# ds8.net
KiCad netlist of a schematic drawn in EAGLE
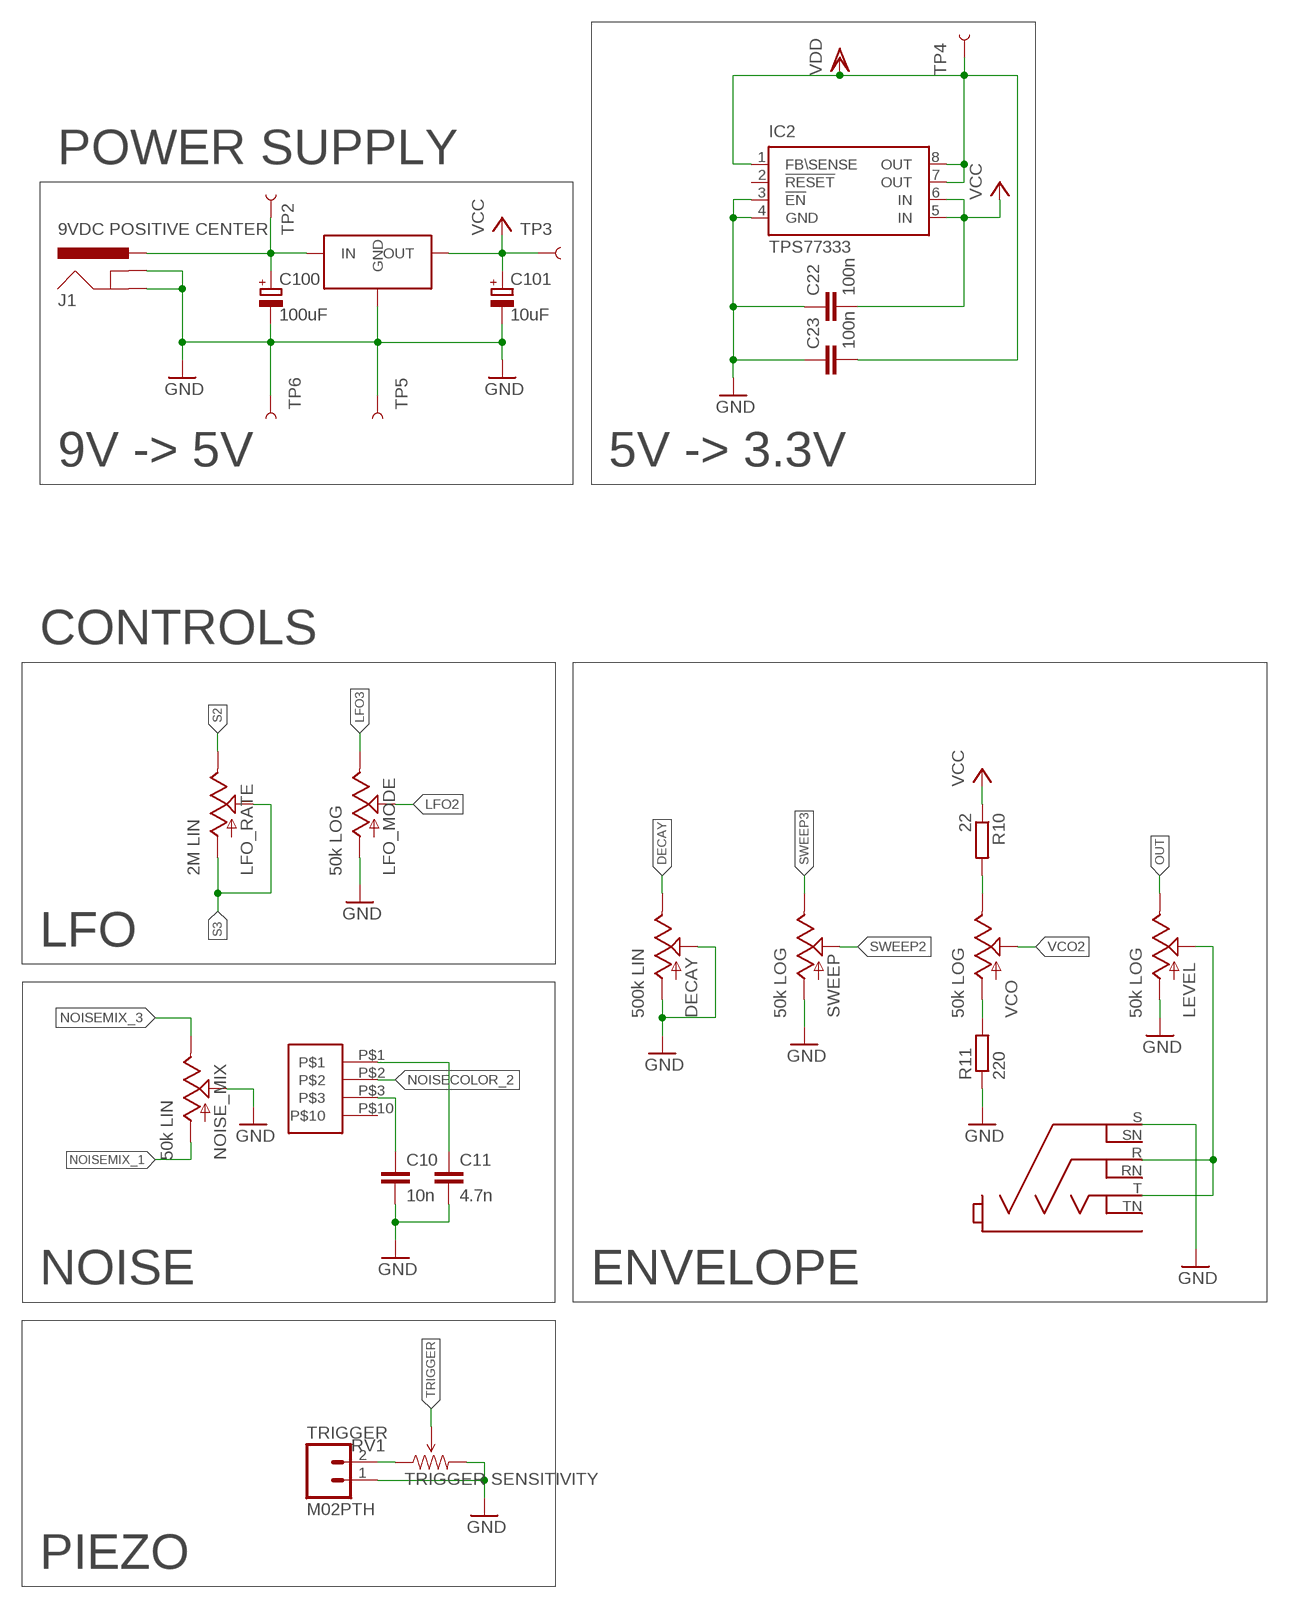
[diagram p0: schematic, sheet 1, part 1 of 2]
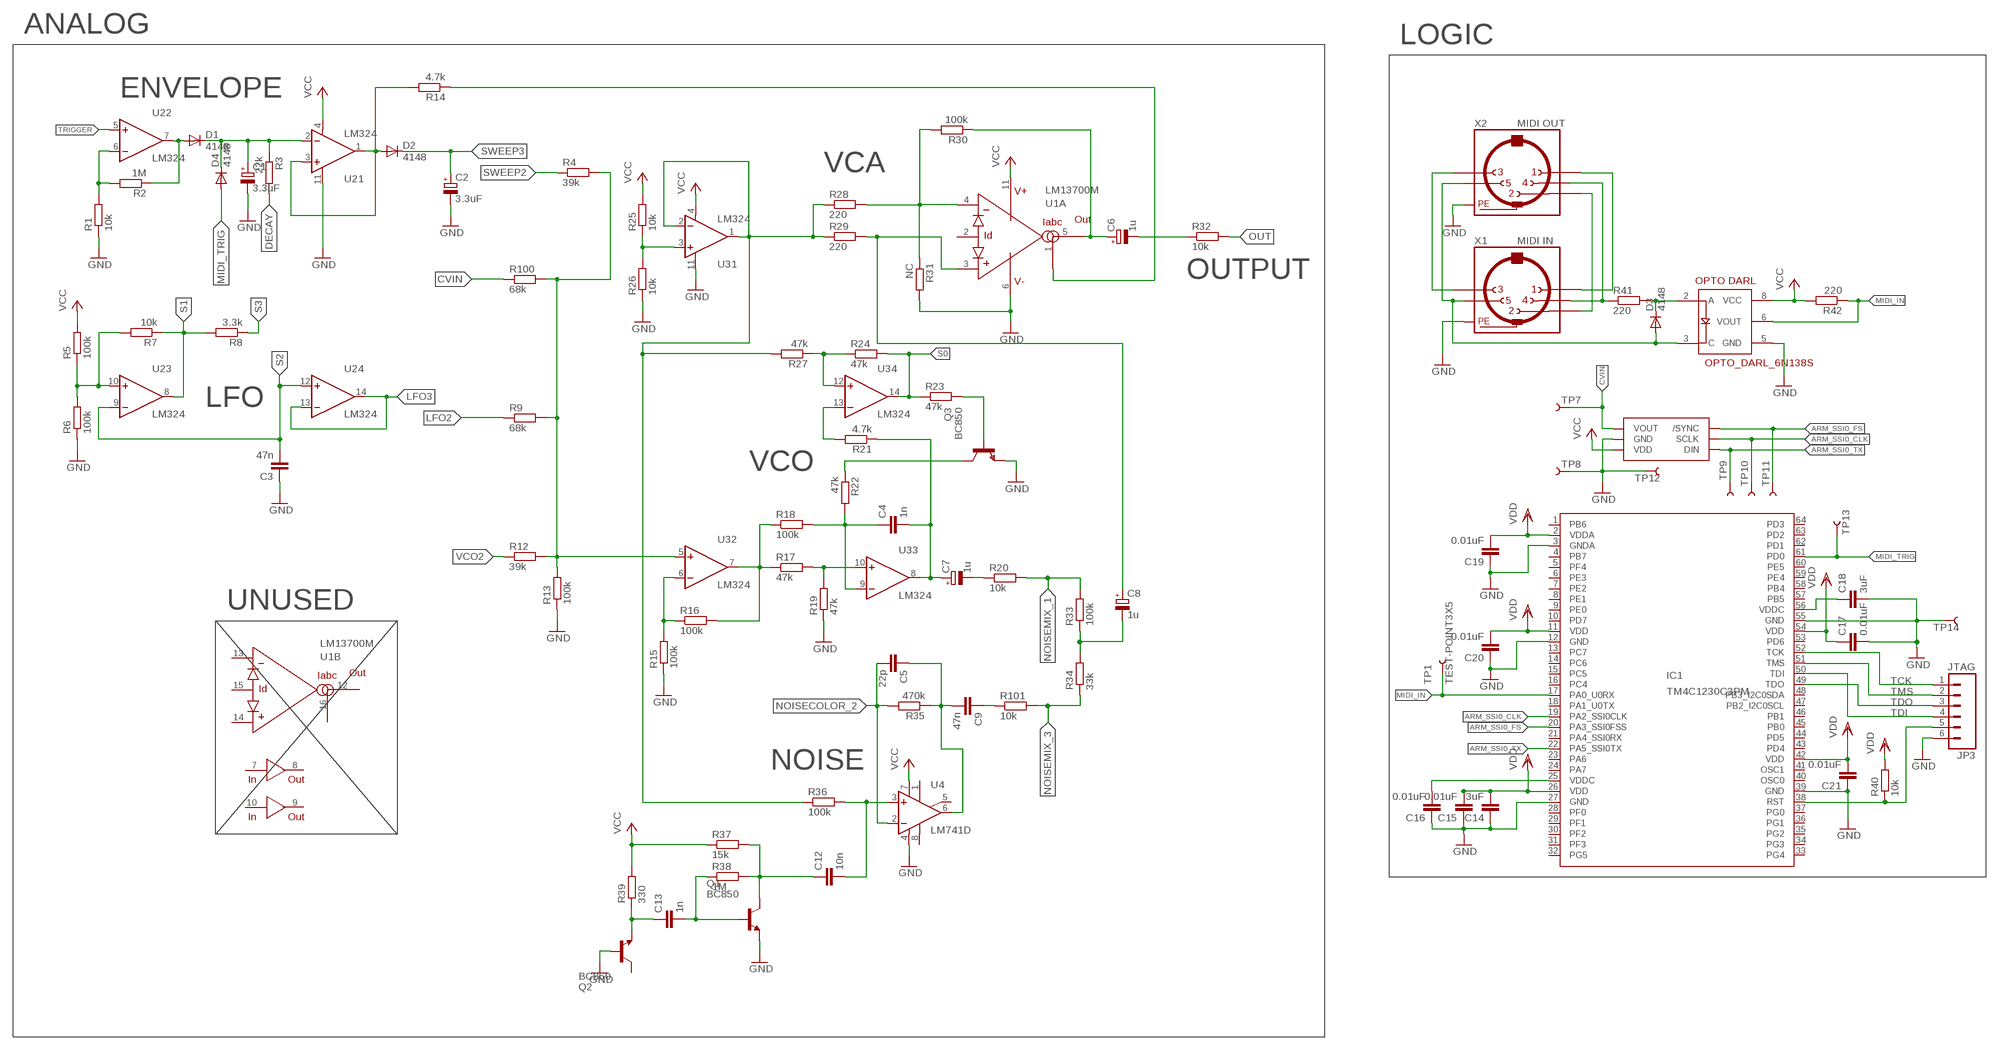
[diagram p1: schematic, sheet 1, part 2 of 2]

(export (version "E")
  (design (tool "Eeschema 10.0.6"))
  (components
    (comp (ref "C1")
      (value "3.3uF")
      (footprint "eagle-import:R_2012-12R")
      (libsource (lib "eagle-import") (part "CPOL-EUR/2012-12R"))
    )
    (comp (ref "C2")
      (value "3.3uF")
      (footprint "eagle-import:R_2012-12R")
      (libsource (lib "eagle-import") (part "CPOL-EUR/2012-12R"))
    )
    (comp (ref "C3")
      (value "47n")
      (footprint "eagle-import:C1206")
      (libsource (lib "eagle-import") (part "C-EUC1206"))
    )
    (comp (ref "C4")
      (value "1n")
      (footprint "eagle-import:C1206")
      (libsource (lib "eagle-import") (part "C-EUC1206"))
    )
    (comp (ref "C5")
      (value "22p")
      (footprint "eagle-import:C1206")
      (libsource (lib "eagle-import") (part "C-EUC1206"))
    )
    (comp (ref "C6")
      (value "1u")
      (footprint "eagle-import:R_2012-12R")
      (libsource (lib "eagle-import") (part "CPOL-EUR/2012-12R"))
    )
    (comp (ref "C7")
      (value "1u")
      (footprint "eagle-import:R_2012-12R")
      (libsource (lib "eagle-import") (part "CPOL-EUR/2012-12R"))
    )
    (comp (ref "C8")
      (value "1u")
      (footprint "eagle-import:R_2012-12R")
      (libsource (lib "eagle-import") (part "CPOL-EUR/2012-12R"))
    )
    (comp (ref "C9")
      (value "47n")
      (footprint "eagle-import:C1206")
      (libsource (lib "eagle-import") (part "C-EUC1206"))
    )
    (comp (ref "C10")
      (value "10n")
      (footprint "eagle-import:C1206")
      (libsource (lib "eagle-import") (part "C-EUC1206"))
    )
    (comp (ref "C11")
      (value "4.7n")
      (footprint "eagle-import:C1206")
      (libsource (lib "eagle-import") (part "C-EUC1206"))
    )
    (comp (ref "C12")
      (value "10n")
      (footprint "eagle-import:C1206")
      (libsource (lib "eagle-import") (part "C-EUC1206"))
    )
    (comp (ref "C13")
      (value "1n")
      (footprint "eagle-import:C1206")
      (libsource (lib "eagle-import") (part "C-EUC1206"))
    )
    (comp (ref "C14")
      (value "3uF")
      (footprint "eagle-import:C1206")
      (libsource (lib "eagle-import") (part "C-EUC1206"))
    )
    (comp (ref "C15")
      (value "0.01uF")
      (footprint "eagle-import:C1206")
      (libsource (lib "eagle-import") (part "C-EUC1206"))
    )
    (comp (ref "C16")
      (value "0.01uF")
      (footprint "eagle-import:C1206")
      (libsource (lib "eagle-import") (part "C-EUC1206"))
    )
    (comp (ref "C17")
      (value "0.01uF")
      (footprint "eagle-import:C1206")
      (libsource (lib "eagle-import") (part "C-EUC1206"))
    )
    (comp (ref "C18")
      (value "3uF")
      (footprint "eagle-import:C1206")
      (libsource (lib "eagle-import") (part "C-EUC1206"))
    )
    (comp (ref "C19")
      (value "0.01uF")
      (footprint "eagle-import:C1206")
      (libsource (lib "eagle-import") (part "C-EUC1206"))
    )
    (comp (ref "C20")
      (value "0.01uF")
      (footprint "eagle-import:C1206")
      (libsource (lib "eagle-import") (part "C-EUC1206"))
    )
    (comp (ref "C21")
      (value "0.01uF")
      (footprint "eagle-import:C1206")
      (libsource (lib "eagle-import") (part "C-EUC1206"))
    )
    (comp (ref "C22")
      (value "100n")
      (footprint "eagle-import:C1206")
      (libsource (lib "eagle-import") (part "C-EUC1206"))
    )
    (comp (ref "C23")
      (value "100n")
      (footprint "eagle-import:C1206")
      (libsource (lib "eagle-import") (part "C-EUC1206"))
    )
    (comp (ref "C100")
      (value "100uF")
      (footprint "eagle-import:PANASONIC_D")
      (libsource (lib "eagle-import") (part "CPOL-EUD"))
    )
    (comp (ref "C101")
      (value "10uF")
      (footprint "eagle-import:R_2012-12R")
      (libsource (lib "eagle-import") (part "CPOL-EUR/2012-12R"))
    )
    (comp (ref "D1")
      (value "4148")
      (footprint "eagle-import:MINIMELF")
      (libsource (lib "eagle-import") (part "DIODE-MINIMELF"))
    )
    (comp (ref "D2")
      (value "4148")
      (footprint "eagle-import:MINIMELF")
      (libsource (lib "eagle-import") (part "DIODE-MINIMELF"))
    )
    (comp (ref "D3")
      (value "4148")
      (footprint "eagle-import:MINIMELF")
      (libsource (lib "eagle-import") (part "DIODE-MINIMELF"))
    )
    (comp (ref "D4")
      (value "4148")
      (footprint "eagle-import:MINIMELF")
      (libsource (lib "eagle-import") (part "DIODE-MINIMELF"))
    )
    (comp (ref "DECAY")
      (value "500k LIN")
      (footprint "eagle-import:ALPS_POT_KIT")
      (libsource (lib "eagle-import") (part "POTALPS-KIT"))
    )
    (comp (ref "IC1")
      (value "TM4C1230C3PM")
      (footprint "eagle-import:LQFP_64")
      (libsource (lib "eagle-import") (part "TM4C1230C3PM"))
    )
    (comp (ref "IC2")
      (value "TPS77333")
      (footprint "eagle-import:SOP-08")
      (fields (field (name "MF") "TEXAS INSTRUMENTS") (field (name "MPN") "TPS77333DGK"))
      (libsource (lib "eagle-import") (part "TPS77333"))
    )
    (comp (ref "IC3")
      (value "DAC7512")
      (footprint "eagle-import:SOT-23-6")
      (libsource (lib "eagle-import") (part "DAC7512"))
    )
    (comp (ref "J1")
      (value "9VDC POSITIVE CENTER")
      (footprint "eagle-import:POWER_JACK_PTH_LOCK")
      (libsource (lib "eagle-import") (part "POWER_JACKPTH_LOCK"))
    )
    (comp (ref "JP3")
      (value "JTAG")
      (footprint "eagle-import:1X06")
      (libsource (lib "eagle-import") (part "M06SIP"))
    )
    (comp (ref "LEVEL")
      (value "50k LOG")
      (footprint "eagle-import:ALPS_POT_KIT")
      (libsource (lib "eagle-import") (part "POTALPS-KIT"))
    )
    (comp (ref "LFO_MODE")
      (value "50k LOG")
      (footprint "eagle-import:ALPS_POT_KIT")
      (libsource (lib "eagle-import") (part "POTALPS-KIT"))
    )
    (comp (ref "LFO_RATE")
      (value "2M LIN")
      (footprint "eagle-import:ALPS_POT_KIT")
      (libsource (lib "eagle-import") (part "POTALPS-KIT"))
    )
    (comp (ref "NOISE_MIX")
      (value "50k LIN")
      (footprint "eagle-import:ALPS_POT_KIT")
      (libsource (lib "eagle-import") (part "POTALPS-KIT"))
    )
    (comp (ref "Q1")
      (value "BC850")
      (footprint "eagle-import:SOT23")
      (libsource (lib "eagle-import") (part "BC850"))
    )
    (comp (ref "Q2")
      (value "BC850")
      (footprint "eagle-import:SOT23")
      (libsource (lib "eagle-import") (part "BC850"))
    )
    (comp (ref "Q3")
      (value "BC850")
      (footprint "eagle-import:SOT23")
      (libsource (lib "eagle-import") (part "BC850"))
    )
    (comp (ref "R1")
      (value "10k")
      (footprint "eagle-import:R0805")
      (libsource (lib "eagle-import") (part "R-EU_R0805"))
    )
    (comp (ref "R2")
      (value "1M")
      (footprint "eagle-import:R0805")
      (libsource (lib "eagle-import") (part "R-EU_R0805"))
    )
    (comp (ref "R3")
      (value "22k")
      (footprint "eagle-import:R0805")
      (libsource (lib "eagle-import") (part "R-EU_R0805"))
    )
    (comp (ref "R4")
      (value "39k")
      (footprint "eagle-import:R0805")
      (libsource (lib "eagle-import") (part "R-EU_R0805"))
    )
    (comp (ref "R5")
      (value "100k")
      (footprint "eagle-import:R0805")
      (libsource (lib "eagle-import") (part "R-EU_R0805"))
    )
    (comp (ref "R6")
      (value "100k")
      (footprint "eagle-import:R0805")
      (libsource (lib "eagle-import") (part "R-EU_R0805"))
    )
    (comp (ref "R7")
      (value "10k")
      (footprint "eagle-import:R0805")
      (libsource (lib "eagle-import") (part "R-EU_R0805"))
    )
    (comp (ref "R8")
      (value "3.3k")
      (footprint "eagle-import:R0805")
      (libsource (lib "eagle-import") (part "R-EU_R0805"))
    )
    (comp (ref "R9")
      (value "68k")
      (footprint "eagle-import:R0805")
      (libsource (lib "eagle-import") (part "R-EU_R0805"))
    )
    (comp (ref "R10")
      (value "22")
      (footprint "eagle-import:R0805")
      (libsource (lib "eagle-import") (part "R-EU_R0805"))
    )
    (comp (ref "R11")
      (value "220")
      (footprint "eagle-import:R0805")
      (libsource (lib "eagle-import") (part "R-EU_R0805"))
    )
    (comp (ref "R12")
      (value "39k")
      (footprint "eagle-import:R0805")
      (libsource (lib "eagle-import") (part "R-EU_R0805"))
    )
    (comp (ref "R13")
      (value "100k")
      (footprint "eagle-import:R0805")
      (libsource (lib "eagle-import") (part "R-EU_R0805"))
    )
    (comp (ref "R14")
      (value "4.7k")
      (footprint "eagle-import:R0805")
      (libsource (lib "eagle-import") (part "R-EU_R0805"))
    )
    (comp (ref "R15")
      (value "100k")
      (footprint "eagle-import:R0805")
      (libsource (lib "eagle-import") (part "R-EU_R0805"))
    )
    (comp (ref "R16")
      (value "100k")
      (footprint "eagle-import:M0805")
      (libsource (lib "eagle-import") (part "R-EU_M0805"))
    )
    (comp (ref "R17")
      (value "47k")
      (footprint "eagle-import:M0805")
      (libsource (lib "eagle-import") (part "R-EU_M0805"))
    )
    (comp (ref "R18")
      (value "100k")
      (footprint "eagle-import:M0805")
      (libsource (lib "eagle-import") (part "R-EU_M0805"))
    )
    (comp (ref "R19")
      (value "47k")
      (footprint "eagle-import:M0805")
      (libsource (lib "eagle-import") (part "R-EU_M0805"))
    )
    (comp (ref "R20")
      (value "10k")
      (footprint "eagle-import:M0805")
      (libsource (lib "eagle-import") (part "R-EU_M0805"))
    )
    (comp (ref "R21")
      (value "4.7k")
      (footprint "eagle-import:M0805")
      (libsource (lib "eagle-import") (part "R-EU_M0805"))
    )
    (comp (ref "R22")
      (value "47k")
      (footprint "eagle-import:M0805")
      (libsource (lib "eagle-import") (part "R-EU_M0805"))
    )
    (comp (ref "R23")
      (value "47k")
      (footprint "eagle-import:M0805")
      (libsource (lib "eagle-import") (part "R-EU_M0805"))
    )
    (comp (ref "R24")
      (value "47k")
      (footprint "eagle-import:M0805")
      (libsource (lib "eagle-import") (part "R-EU_M0805"))
    )
    (comp (ref "R25")
      (value "10k")
      (footprint "eagle-import:M0805")
      (libsource (lib "eagle-import") (part "R-EU_M0805"))
    )
    (comp (ref "R26")
      (value "10k")
      (footprint "eagle-import:M0805")
      (libsource (lib "eagle-import") (part "R-EU_M0805"))
    )
    (comp (ref "R27")
      (value "47k")
      (footprint "eagle-import:M0805")
      (libsource (lib "eagle-import") (part "R-EU_M0805"))
    )
    (comp (ref "R28")
      (value "220")
      (footprint "eagle-import:M0805")
      (libsource (lib "eagle-import") (part "R-EU_M0805"))
    )
    (comp (ref "R29")
      (value "220")
      (footprint "eagle-import:M0805")
      (libsource (lib "eagle-import") (part "R-EU_M0805"))
    )
    (comp (ref "R30")
      (value "100k")
      (footprint "eagle-import:M0805")
      (libsource (lib "eagle-import") (part "R-EU_M0805"))
    )
    (comp (ref "R31")
      (value "NC")
      (footprint "eagle-import:M0805")
      (libsource (lib "eagle-import") (part "R-EU_M0805"))
    )
    (comp (ref "R32")
      (value "10k")
      (footprint "eagle-import:M0805")
      (libsource (lib "eagle-import") (part "R-EU_M0805"))
    )
    (comp (ref "R33")
      (value "100k")
      (footprint "eagle-import:M0805")
      (libsource (lib "eagle-import") (part "R-EU_M0805"))
    )
    (comp (ref "R34")
      (value "33k")
      (footprint "eagle-import:M0805")
      (libsource (lib "eagle-import") (part "R-EU_M0805"))
    )
    (comp (ref "R35")
      (value "470k")
      (footprint "eagle-import:M0805")
      (libsource (lib "eagle-import") (part "R-EU_M0805"))
    )
    (comp (ref "R36")
      (value "100k")
      (footprint "eagle-import:M0805")
      (libsource (lib "eagle-import") (part "R-EU_M0805"))
    )
    (comp (ref "R37")
      (value "15k")
      (footprint "eagle-import:M0805")
      (libsource (lib "eagle-import") (part "R-EU_M0805"))
    )
    (comp (ref "R38")
      (value "1M")
      (footprint "eagle-import:M0805")
      (libsource (lib "eagle-import") (part "R-EU_M0805"))
    )
    (comp (ref "R39")
      (value "330")
      (footprint "eagle-import:M0805")
      (libsource (lib "eagle-import") (part "R-EU_M0805"))
    )
    (comp (ref "R40")
      (value "10k")
      (footprint "eagle-import:M0805")
      (libsource (lib "eagle-import") (part "R-EU_M0805"))
    )
    (comp (ref "R41")
      (value "220")
      (footprint "eagle-import:R0805")
      (libsource (lib "eagle-import") (part "R-EU_R0805"))
    )
    (comp (ref "R42")
      (value "220")
      (footprint "eagle-import:R0805")
      (libsource (lib "eagle-import") (part "R-EU_R0805"))
    )
    (comp (ref "R100")
      (value "68k")
      (footprint "eagle-import:R0805")
      (libsource (lib "eagle-import") (part "R-EU_R0805"))
    )
    (comp (ref "R101")
      (value "10k")
      (footprint "eagle-import:M0805")
      (libsource (lib "eagle-import") (part "R-EU_M0805"))
    )
    (comp (ref "RV1")
      (value "TRIGGER SENSITIVITY")
      (footprint "eagle-import:TRIMPOT-5MM-V2")
      (libsource (lib "eagle-import") (part "TRIMPOT"))
    )
    (comp (ref "SWEEP")
      (value "50k LOG")
      (footprint "eagle-import:ALPS_POT_KIT")
      (libsource (lib "eagle-import") (part "POTALPS-KIT"))
    )
    (comp (ref "TP1")
      (value "TEST-POINT3X5")
      (footprint "eagle-import:PAD.03X.05")
      (libsource (lib "eagle-import") (part "TEST-POINT3X5"))
    )
    (comp (ref "TP2")
      (value "TEST-POINT3X5")
      (footprint "eagle-import:PAD.03X.05")
      (libsource (lib "eagle-import") (part "TEST-POINT3X5"))
    )
    (comp (ref "TP3")
      (value "TEST-POINT3X5")
      (footprint "eagle-import:PAD.03X.05")
      (libsource (lib "eagle-import") (part "TEST-POINT3X5"))
    )
    (comp (ref "TP4")
      (value "TEST-POINT3X5")
      (footprint "eagle-import:PAD.03X.05")
      (libsource (lib "eagle-import") (part "TEST-POINT3X5"))
    )
    (comp (ref "TP5")
      (value "TEST-POINT3X5")
      (footprint "eagle-import:PAD.03X.05")
      (libsource (lib "eagle-import") (part "TEST-POINT3X5"))
    )
    (comp (ref "TP6")
      (value "TEST-POINT3X5")
      (footprint "eagle-import:PAD.03X.05")
      (libsource (lib "eagle-import") (part "TEST-POINT3X5"))
    )
    (comp (ref "TP7")
      (value "TEST-POINT3X5")
      (footprint "eagle-import:PAD.03X.05")
      (libsource (lib "eagle-import") (part "TEST-POINT3X5"))
    )
    (comp (ref "TP8")
      (value "TEST-POINT3X5")
      (footprint "eagle-import:PAD.03X.05")
      (libsource (lib "eagle-import") (part "TEST-POINT3X5"))
    )
    (comp (ref "TP9")
      (value "TEST-POINT3X5")
      (footprint "eagle-import:PAD.03X.05")
      (libsource (lib "eagle-import") (part "TEST-POINT3X5"))
    )
    (comp (ref "TP10")
      (value "TEST-POINT3X5")
      (footprint "eagle-import:PAD.03X.05")
      (libsource (lib "eagle-import") (part "TEST-POINT3X5"))
    )
    (comp (ref "TP11")
      (value "TEST-POINT3X5")
      (footprint "eagle-import:PAD.03X.05")
      (libsource (lib "eagle-import") (part "TEST-POINT3X5"))
    )
    (comp (ref "TP12")
      (value "TEST-POINT3X5")
      (footprint "eagle-import:PAD.03X.05")
      (libsource (lib "eagle-import") (part "TEST-POINT3X5"))
    )
    (comp (ref "TP13")
      (value "TEST-POINT3X5")
      (footprint "eagle-import:PAD.03X.05")
      (libsource (lib "eagle-import") (part "TEST-POINT3X5"))
    )
    (comp (ref "TP14")
      (value "TEST-POINT3X5")
      (footprint "eagle-import:PAD.03X.05")
      (libsource (lib "eagle-import") (part "TEST-POINT3X5"))
    )
    (comp (ref "TRIGGER")
      (value "M02PTH")
      (footprint "eagle-import:1X02")
      (libsource (lib "eagle-import") (part "M02PTH"))
    )
    (comp (ref "U$1")
      (value "6.35MMJACK")
      (footprint "eagle-import:NMJ6HCD3")
      (libsource (lib "eagle-import") (part "6.35MMJACK"))
    )
    (comp (ref "U$3")
      (value "ALPS_SRBV")
      (footprint "eagle-import:ALPS_SRBV")
      (libsource (lib "eagle-import") (part "ALPS_SRBV"))
    )
    (comp (ref "U$4")
      (value "OPTO_DARL_6N138S")
      (footprint "eagle-import:8-SMD")
      (libsource (lib "eagle-import") (part "OPTO_DARL_6N138S"))
    )
    (comp (ref "U1")
      (value "LM13700M")
      (footprint "eagle-import:DS8_SO16")
      (libsource (lib "eagle-import") (part "DS8_LM13700M"))
    )
    (comp (ref "U2")
      (value "LM324")
      (footprint "eagle-import:SOIC-14")
      (libsource (lib "eagle-import") (part "LM324"))
    )
    (comp (ref "U3")
      (value "LM324")
      (footprint "eagle-import:SOIC-14")
      (libsource (lib "eagle-import") (part "LM324"))
    )
    (comp (ref "U4")
      (value "LM741D")
      (footprint "eagle-import:SO08")
      (libsource (lib "eagle-import") (part "741DLM"))
    )
    (comp (ref "U100")
      (value "VREG-7805-DPAK2")
      (footprint "eagle-import:VREG-7805-DPAK2")
      (libsource (lib "eagle-import") (part "VREG-7805-DPAK2"))
    )
    (comp (ref "VCO")
      (value "50k LOG")
      (footprint "eagle-import:ALPS_POT_KIT")
      (libsource (lib "eagle-import") (part "POTALPS-KIT"))
    )
    (comp (ref "X1")
      (value "MIDI IN")
      (footprint "eagle-import:MAB5SH")
      (libsource (lib "eagle-import") (part "MAB5SH"))
    )
    (comp (ref "X2")
      (value "MIDI OUT")
      (footprint "eagle-import:MAB5SH")
      (fields (field (name "OC_FARNELL") "809883") (field (name "OC_NEWARK") "unknown"))
      (libsource (lib "eagle-import") (part "MAB5SH"))
    )
  )
  (nets
    (net (code "1") (name "/TCK") (class "Default")
      (node (ref "IC1") (pin "52") (pinfunction "TCK_52") (pintype "input"))
      (node (ref "JP3") (pin "1") (pinfunction "1_1") (pintype "passive"))
    )
    (net (code "2") (name "/TDI") (class "Default")
      (node (ref "IC1") (pin "50") (pinfunction "TDI_50") (pintype "input"))
      (node (ref "JP3") (pin "4") (pinfunction "4_4") (pintype "passive"))
    )
    (net (code "3") (name "/TDO") (class "Default")
      (node (ref "IC1") (pin "49") (pinfunction "TDO_49") (pintype "output"))
      (node (ref "JP3") (pin "3") (pinfunction "3_3") (pintype "passive"))
    )
    (net (code "4") (name "/TMS") (class "Default")
      (node (ref "IC1") (pin "51") (pinfunction "TMS_51") (pintype "input"))
      (node (ref "JP3") (pin "2") (pinfunction "2_2") (pintype "passive"))
    )
    (net (code "5") (name "ARM_SSI0_CLK") (class "Default")
      (node (ref "IC1") (pin "19") (pinfunction "PA2_SSI0CLK_19") (pintype "bidirectional"))
      (node (ref "IC3") (pin "5") (pinfunction "SCLK_5") (pintype "bidirectional"))
      (node (ref "TP10") (pin "P$1") (pinfunction "1_P$1") (pintype "bidirectional"))
    )
    (net (code "6") (name "ARM_SSI0_FS") (class "Default")
      (node (ref "IC1") (pin "20") (pinfunction "PA3_SSI0FSS_20") (pintype "bidirectional"))
      (node (ref "IC3") (pin "6") (pinfunction "/SYNC_6") (pintype "bidirectional"))
      (node (ref "TP11") (pin "P$1") (pinfunction "1_P$1") (pintype "bidirectional"))
    )
    (net (code "7") (name "ARM_SSI0_TX") (class "Default")
      (node (ref "IC1") (pin "22") (pinfunction "PA5_SSI0TX_22") (pintype "bidirectional"))
      (node (ref "IC3") (pin "4") (pinfunction "DIN_4") (pintype "bidirectional"))
      (node (ref "TP9") (pin "P$1") (pinfunction "1_P$1") (pintype "bidirectional"))
    )
    (net (code "8") (name "CVIN") (class "Default")
      (node (ref "IC3") (pin "1") (pinfunction "VOUT_1") (pintype "output"))
      (node (ref "R100") (pin "1") (pinfunction "1_1") (pintype "passive"))
      (node (ref "TP7") (pin "P$1") (pinfunction "1_P$1") (pintype "bidirectional"))
    )
    (net (code "9") (name "DECAY") (class "Default")
      (node (ref "DECAY") (pin "P$1") (pinfunction "E_P$1") (pintype "passive"))
      (node (ref "R3") (pin "2") (pinfunction "2_2") (pintype "passive"))
    )
    (net (code "10") (name "GND") (class "Default")
      (node (ref "C1") (pin "-") (pinfunction "-_-") (pintype "passive"))
      (node (ref "C10") (pin "2") (pinfunction "2_2") (pintype "passive"))
      (node (ref "C100") (pin "-") (pinfunction "-_-") (pintype "passive"))
      (node (ref "C101") (pin "-") (pinfunction "-_-") (pintype "passive"))
      (node (ref "C11") (pin "2") (pinfunction "2_2") (pintype "passive"))
      (node (ref "C14") (pin "1") (pinfunction "1_1") (pintype "passive"))
      (node (ref "C15") (pin "1") (pinfunction "1_1") (pintype "passive"))
      (node (ref "C16") (pin "1") (pinfunction "1_1") (pintype "passive"))
      (node (ref "C17") (pin "2") (pinfunction "2_2") (pintype "passive"))
      (node (ref "C18") (pin "2") (pinfunction "2_2") (pintype "passive"))
      (node (ref "C19") (pin "1") (pinfunction "1_1") (pintype "passive"))
      (node (ref "C2") (pin "-") (pinfunction "-_-") (pintype "passive"))
      (node (ref "C20") (pin "1") (pinfunction "1_1") (pintype "passive"))
      (node (ref "C21") (pin "1") (pinfunction "1_1") (pintype "passive"))
      (node (ref "C22") (pin "1") (pinfunction "1_1") (pintype "passive"))
      (node (ref "C23") (pin "1") (pinfunction "1_1") (pintype "passive"))
      (node (ref "C3") (pin "1") (pinfunction "1_1") (pintype "passive"))
      (node (ref "DECAY") (pin "P$2") (pinfunction "S_P$2") (pintype "passive"))
      (node (ref "DECAY") (pin "P$3") (pinfunction "A_P$3") (pintype "passive"))
      (node (ref "IC1") (pin "12") (pinfunction "GND_12") (pintype "power_in"))
      (node (ref "IC1") (pin "27") (pinfunction "GND_27") (pintype "power_in"))
      (node (ref "IC1") (pin "3") (pinfunction "GNDA_3") (pintype "power_in"))
      (node (ref "IC1") (pin "39") (pinfunction "GND_39") (pintype "power_in"))
      (node (ref "IC1") (pin "55") (pinfunction "GND_55") (pintype "power_in"))
      (node (ref "IC2") (pin "3") (pinfunction "~{EN}_3") (pintype "input"))
      (node (ref "IC2") (pin "4") (pinfunction "GND_4") (pintype "power_in"))
      (node (ref "IC3") (pin "2") (pinfunction "GND_2") (pintype "power_in"))
      (node (ref "J1") (pin "GND") (pinfunction "GND_GND") (pintype "bidirectional"))
      (node (ref "J1") (pin "GNDBREAK") (pinfunction "GNDBREAK_GNDBREAK") (pintype "bidirectional"))
      (node (ref "JP3") (pin "6") (pinfunction "6_6") (pintype "passive"))
      (node (ref "LEVEL") (pin "P$3") (pinfunction "A_P$3") (pintype "passive"))
      (node (ref "LFO_MODE") (pin "P$3") (pinfunction "A_P$3") (pintype "passive"))
      (node (ref "NOISE_MIX") (pin "P$2") (pinfunction "S_P$2") (pintype "passive"))
      (node (ref "Q1") (pin "2") (pinfunction "E_2") (pintype "passive"))
      (node (ref "Q2") (pin "1") (pinfunction "B_1") (pintype "passive"))
      (node (ref "Q3") (pin "2") (pinfunction "E_2") (pintype "passive"))
      (node (ref "R1") (pin "1") (pinfunction "1_1") (pintype "passive"))
      (node (ref "R11") (pin "1") (pinfunction "1_1") (pintype "passive"))
      (node (ref "R13") (pin "1") (pinfunction "1_1") (pintype "passive"))
      (node (ref "R15") (pin "1") (pinfunction "1_1") (pintype "passive"))
      (node (ref "R19") (pin "1") (pinfunction "1_1") (pintype "passive"))
      (node (ref "R26") (pin "1") (pinfunction "1_1") (pintype "passive"))
      (node (ref "R31") (pin "2") (pinfunction "2_2") (pintype "passive"))
      (node (ref "R6") (pin "1") (pinfunction "1_1") (pintype "passive"))
      (node (ref "RV1") (pin "C") (pinfunction "CW_C") (pintype "passive"))
      (node (ref "SWEEP") (pin "P$3") (pinfunction "A_P$3") (pintype "passive"))
      (node (ref "TP12") (pin "P$1") (pinfunction "1_P$1") (pintype "bidirectional"))
      (node (ref "TP14") (pin "P$1") (pinfunction "1_P$1") (pintype "bidirectional"))
      (node (ref "TP5") (pin "P$1") (pinfunction "1_P$1") (pintype "bidirectional"))
      (node (ref "TP6") (pin "P$1") (pinfunction "1_P$1") (pintype "bidirectional"))
      (node (ref "TP8") (pin "P$1") (pinfunction "1_P$1") (pintype "bidirectional"))
      (node (ref "TRIGGER") (pin "1") (pinfunction "1_1") (pintype "passive"))
      (node (ref "U$1") (pin "S") (pinfunction "S_S") (pintype "bidirectional"))
      (node (ref "U$4") (pin "5") (pinfunction "GND_5") (pintype "bidirectional"))
      (node (ref "U1") (pin "6") (pinfunction "V-_6") (pintype "bidirectional"))
      (node (ref "U100") (pin "GND") (pinfunction "GND_GND") (pintype "bidirectional"))
      (node (ref "U2") (pin "11") (pinfunction "V-_11") (pintype "power_in"))
      (node (ref "U3") (pin "11") (pinfunction "V-_11") (pintype "power_in"))
      (node (ref "U4") (pin "4") (pinfunction "V-_4") (pintype "power_in"))
      (node (ref "X1") (pin "PE") (pinfunction "PE_PE") (pintype "power_in"))
      (node (ref "X1") (pin "PE@") (pinfunction "PE_PE@") (pintype "power_in"))
      (node (ref "X2") (pin "PE") (pinfunction "PE_PE") (pintype "power_in"))
      (node (ref "X2") (pin "PE@") (pinfunction "PE_PE@") (pintype "power_in"))
    )
    (net (code "11") (name "LFO2") (class "Default")
      (node (ref "LFO_MODE") (pin "P$2") (pinfunction "S_P$2") (pintype "passive"))
      (node (ref "R9") (pin "1") (pinfunction "1_1") (pintype "passive"))
    )
    (net (code "12") (name "LFO3") (class "Default")
      (node (ref "LFO_MODE") (pin "P$1") (pinfunction "E_P$1") (pintype "passive"))
      (node (ref "U2") (pin "13") (pinfunction "-IN_13") (pintype "input"))
      (node (ref "U2") (pin "14") (pinfunction "OUT_14") (pintype "output"))
    )
    (net (code "13") (name "MIDI_IN") (class "Default")
      (node (ref "IC1") (pin "17") (pinfunction "PA0_U0RX_17") (pintype "bidirectional"))
      (node (ref "R42") (pin "1") (pinfunction "1_1") (pintype "passive"))
      (node (ref "TP1") (pin "P$1") (pinfunction "1_P$1") (pintype "bidirectional"))
      (node (ref "U$4") (pin "6") (pinfunction "VOUT_6") (pintype "bidirectional"))
    )
    (net (code "14") (name "MIDI_TRIG") (class "Default")
      (node (ref "D4") (pin "A") (pinfunction "A_A") (pintype "passive"))
      (node (ref "IC1") (pin "61") (pinfunction "PD0_61") (pintype "bidirectional"))
      (node (ref "TP13") (pin "P$1") (pinfunction "1_P$1") (pintype "bidirectional"))
    )
    (net (code "15") (name "NOISECOLOR_2") (class "Default")
      (node (ref "C5") (pin "2") (pinfunction "2_2") (pintype "passive"))
      (node (ref "R35") (pin "2") (pinfunction "2_2") (pintype "passive"))
      (node (ref "U$3") (pin "P$2") (pinfunction "P$2_P$2") (pintype "bidirectional"))
      (node (ref "U4") (pin "2") (pinfunction "-IN_2") (pintype "input"))
    )
    (net (code "16") (name "NOISEMIX_1") (class "Default")
      (node (ref "NOISE_MIX") (pin "P$3") (pinfunction "A_P$3") (pintype "passive"))
      (node (ref "R20") (pin "2") (pinfunction "2_2") (pintype "passive"))
      (node (ref "R33") (pin "2") (pinfunction "2_2") (pintype "passive"))
    )
    (net (code "17") (name "NOISEMIX_3") (class "Default")
      (node (ref "NOISE_MIX") (pin "P$1") (pinfunction "E_P$1") (pintype "passive"))
      (node (ref "R101") (pin "2") (pinfunction "2_2") (pintype "passive"))
      (node (ref "R34") (pin "1") (pinfunction "1_1") (pintype "passive"))
    )
    (net (code "18") (name "Net-(C6-Pad-)") (class "Default")
      (node (ref "C6") (pin "-") (pinfunction "-_-") (pintype "passive"))
      (node (ref "R32") (pin "1") (pinfunction "1_1") (pintype "passive"))
    )
    (net (code "19") (name "Net-(C7-Pad-)") (class "Default")
      (node (ref "C7") (pin "-") (pinfunction "-_-") (pintype "passive"))
      (node (ref "R20") (pin "1") (pinfunction "1_1") (pintype "passive"))
    )
    (net (code "20") (name "Net-(C8-Pad-)") (class "Default")
      (node (ref "C8") (pin "-") (pinfunction "-_-") (pintype "passive"))
      (node (ref "R33") (pin "1") (pinfunction "1_1") (pintype "passive"))
      (node (ref "R34") (pin "2") (pinfunction "2_2") (pintype "passive"))
    )
    (net (code "21") (name "Net-(C9-Pad1)") (class "Default")
      (node (ref "C9") (pin "1") (pinfunction "1_1") (pintype "passive"))
      (node (ref "R101") (pin "1") (pinfunction "1_1") (pintype "passive"))
    )
    (net (code "22") (name "Net-(C10-Pad1)") (class "Default")
      (node (ref "C10") (pin "1") (pinfunction "1_1") (pintype "passive"))
      (node (ref "U$3") (pin "P$3") (pinfunction "P$3_P$3") (pintype "bidirectional"))
    )
    (net (code "23") (name "Net-(C11-Pad1)") (class "Default")
      (node (ref "C11") (pin "1") (pinfunction "1_1") (pintype "passive"))
      (node (ref "U$3") (pin "P$1") (pinfunction "P$1_P$1") (pintype "bidirectional"))
    )
    (net (code "24") (name "Net-(C16-Pad2)") (class "Default")
      (node (ref "C16") (pin "2") (pinfunction "2_2") (pintype "passive"))
      (node (ref "IC1") (pin "25") (pinfunction "VDDC_25") (pintype "power_in"))
    )
    (net (code "25") (name "Net-(C18-Pad1)") (class "Default")
      (node (ref "C18") (pin "1") (pinfunction "1_1") (pintype "passive"))
      (node (ref "IC1") (pin "56") (pinfunction "VDDC_56") (pintype "power_in"))
    )
    (net (code "26") (name "Net-(IC1-RST)") (class "Default")
      (node (ref "IC1") (pin "38") (pinfunction "RST_38") (pintype "passive"))
      (node (ref "JP3") (pin "5") (pinfunction "5_5") (pintype "passive"))
      (node (ref "R40") (pin "1") (pinfunction "1_1") (pintype "passive"))
    )
    (net (code "27") (name "Net-(LEVEL-S)") (class "Default")
      (node (ref "LEVEL") (pin "P$2") (pinfunction "S_P$2") (pintype "passive"))
      (node (ref "U$1") (pin "R") (pinfunction "R_R") (pintype "bidirectional"))
      (node (ref "U$1") (pin "T") (pinfunction "T_T") (pintype "bidirectional"))
    )
    (net (code "28") (name "Net-(Q1-B)") (class "Default")
      (node (ref "C13") (pin "2") (pinfunction "2_2") (pintype "passive"))
      (node (ref "Q1") (pin "1") (pinfunction "B_1") (pintype "passive"))
      (node (ref "R38") (pin "1") (pinfunction "1_1") (pintype "passive"))
    )
    (net (code "29") (name "Net-(Q1-C)") (class "Default")
      (node (ref "C12") (pin "1") (pinfunction "1_1") (pintype "passive"))
      (node (ref "Q1") (pin "3") (pinfunction "C_3") (pintype "passive"))
      (node (ref "R37") (pin "2") (pinfunction "2_2") (pintype "passive"))
      (node (ref "R38") (pin "2") (pinfunction "2_2") (pintype "passive"))
    )
    (net (code "30") (name "Net-(Q2-E)") (class "Default")
      (node (ref "C13") (pin "1") (pinfunction "1_1") (pintype "passive"))
      (node (ref "Q2") (pin "2") (pinfunction "E_2") (pintype "passive"))
      (node (ref "R39") (pin "1") (pinfunction "1_1") (pintype "passive"))
    )
    (net (code "31") (name "Net-(Q3-B)") (class "Default")
      (node (ref "Q3") (pin "1") (pinfunction "B_1") (pintype "passive"))
      (node (ref "R23") (pin "2") (pinfunction "2_2") (pintype "passive"))
    )
    (net (code "32") (name "Net-(Q3-C)") (class "Default")
      (node (ref "Q3") (pin "3") (pinfunction "C_3") (pintype "passive"))
      (node (ref "R22") (pin "1") (pinfunction "1_1") (pintype "passive"))
    )
    (net (code "33") (name "Net-(R41-Pad1)") (class "Default")
      (node (ref "R41") (pin "1") (pinfunction "1_1") (pintype "passive"))
      (node (ref "X1") (pin "4") (pinfunction "4_4") (pintype "passive"))
      (node (ref "X2") (pin "4") (pinfunction "4_4") (pintype "passive"))
    )
    (net (code "34") (name "Net-(RV1-CCW)") (class "Default")
      (node (ref "RV1") (pin "A") (pinfunction "CCW_A") (pintype "passive"))
      (node (ref "TRIGGER") (pin "2") (pinfunction "2_2") (pintype "passive"))
    )
    (net (code "35") (name "Net-(TP2-1)") (class "Default")
      (node (ref "C100") (pin "+") (pinfunction "+_+") (pintype "passive"))
      (node (ref "J1") (pin "PWR") (pinfunction "PWR_PWR") (pintype "bidirectional"))
      (node (ref "TP2") (pin "P$1") (pinfunction "1_P$1") (pintype "bidirectional"))
      (node (ref "U100") (pin "VIN") (pinfunction "IN_VIN") (pintype "bidirectional"))
    )
    (net (code "36") (name "Net-(U$4-A)") (class "Default")
      (node (ref "D3") (pin "C") (pinfunction "C_C") (pintype "passive"))
      (node (ref "R41") (pin "2") (pinfunction "2_2") (pintype "passive"))
      (node (ref "U$4") (pin "2") (pinfunction "A_2") (pintype "bidirectional"))
    )
    (net (code "37") (name "Net-(U$4-C)") (class "Default")
      (node (ref "D3") (pin "A") (pinfunction "A_A") (pintype "passive"))
      (node (ref "U$4") (pin "3") (pinfunction "C_3") (pintype "bidirectional"))
      (node (ref "X1") (pin "5") (pinfunction "5_5") (pintype "passive"))
      (node (ref "X2") (pin "5") (pinfunction "5_5") (pintype "passive"))
    )
    (net (code "38") (name "Net-(U1A-+IN)") (class "Default")
      (node (ref "C8") (pin "+") (pinfunction "+_+") (pintype "passive"))
      (node (ref "R29") (pin "2") (pinfunction "2_2") (pintype "passive"))
      (node (ref "U1") (pin "3") (pinfunction "+IN_3") (pintype "bidirectional"))
    )
    (net (code "39") (name "Net-(U1A--IN)") (class "Default")
      (node (ref "R28") (pin "2") (pinfunction "2_2") (pintype "passive"))
      (node (ref "R30") (pin "2") (pinfunction "2_2") (pintype "passive"))
      (node (ref "R31") (pin "1") (pinfunction "1_1") (pintype "passive"))
      (node (ref "U1") (pin "4") (pinfunction "-IN_4") (pintype "bidirectional"))
    )
    (net (code "40") (name "Net-(U1A-IABC)") (class "Default")
      (node (ref "R14") (pin "1") (pinfunction "1_1") (pintype "passive"))
      (node (ref "U1") (pin "1") (pinfunction "IABC_1") (pintype "bidirectional"))
    )
    (net (code "41") (name "Net-(U1A-OUT)") (class "Default")
      (node (ref "C6") (pin "+") (pinfunction "+_+") (pintype "passive"))
      (node (ref "R30") (pin "1") (pinfunction "1_1") (pintype "passive"))
      (node (ref "U1") (pin "5") (pinfunction "OUT_5") (pintype "bidirectional"))
    )
    (net (code "42") (name "Net-(U2A-+IN)") (class "Default")
      (node (ref "D2") (pin "A") (pinfunction "A_A") (pintype "passive"))
      (node (ref "R14") (pin "2") (pinfunction "2_2") (pintype "passive"))
      (node (ref "U2") (pin "1") (pinfunction "OUT_1") (pintype "output"))
      (node (ref "U2") (pin "3") (pinfunction "+IN_3") (pintype "input"))
    )
    (net (code "43") (name "Net-(U2A--IN)") (class "Default")
      (node (ref "C1") (pin "+") (pinfunction "+_+") (pintype "passive"))
      (node (ref "D1") (pin "C") (pinfunction "C_C") (pintype "passive"))
      (node (ref "D4") (pin "C") (pinfunction "C_C") (pintype "passive"))
      (node (ref "R3") (pin "1") (pinfunction "1_1") (pintype "passive"))
      (node (ref "U2") (pin "2") (pinfunction "-IN_2") (pintype "input"))
    )
    (net (code "44") (name "Net-(U2B--IN)") (class "Default")
      (node (ref "R1") (pin "2") (pinfunction "2_2") (pintype "passive"))
      (node (ref "R2") (pin "2") (pinfunction "2_2") (pintype "passive"))
      (node (ref "U2") (pin "6") (pinfunction "-IN_6") (pintype "input"))
    )
    (net (code "45") (name "Net-(U2B-OUT)") (class "Default")
      (node (ref "D1") (pin "A") (pinfunction "A_A") (pintype "passive"))
      (node (ref "R2") (pin "1") (pinfunction "1_1") (pintype "passive"))
      (node (ref "U2") (pin "7") (pinfunction "OUT_7") (pintype "output"))
    )
    (net (code "46") (name "Net-(U2C-+IN)") (class "Default")
      (node (ref "R5") (pin "1") (pinfunction "1_1") (pintype "passive"))
      (node (ref "R6") (pin "2") (pinfunction "2_2") (pintype "passive"))
      (node (ref "R7") (pin "2") (pinfunction "2_2") (pintype "passive"))
      (node (ref "U2") (pin "10") (pinfunction "+IN_10") (pintype "input"))
    )
    (net (code "47") (name "Net-(U3A-+IN)") (class "Default")
      (node (ref "R25") (pin "1") (pinfunction "1_1") (pintype "passive"))
      (node (ref "R26") (pin "2") (pinfunction "2_2") (pintype "passive"))
      (node (ref "U3") (pin "3") (pinfunction "+IN_3") (pintype "input"))
    )
    (net (code "48") (name "Net-(U3A--IN)") (class "Default")
      (node (ref "R27") (pin "2") (pinfunction "2_2") (pintype "passive"))
      (node (ref "R28") (pin "1") (pinfunction "1_1") (pintype "passive"))
      (node (ref "R29") (pin "1") (pinfunction "1_1") (pintype "passive"))
      (node (ref "R36") (pin "1") (pinfunction "1_1") (pintype "passive"))
      (node (ref "U3") (pin "1") (pinfunction "OUT_1") (pintype "output"))
      (node (ref "U3") (pin "2") (pinfunction "-IN_2") (pintype "input"))
    )
    (net (code "49") (name "Net-(U3B-+IN)") (class "Default")
      (node (ref "R100") (pin "2") (pinfunction "2_2") (pintype "passive"))
      (node (ref "R12") (pin "2") (pinfunction "2_2") (pintype "passive"))
      (node (ref "R13") (pin "2") (pinfunction "2_2") (pintype "passive"))
      (node (ref "R4") (pin "2") (pinfunction "2_2") (pintype "passive"))
      (node (ref "R9") (pin "2") (pinfunction "2_2") (pintype "passive"))
      (node (ref "U3") (pin "5") (pinfunction "+IN_5") (pintype "input"))
    )
    (net (code "50") (name "Net-(U3B--IN)") (class "Default")
      (node (ref "R15") (pin "2") (pinfunction "2_2") (pintype "passive"))
      (node (ref "R16") (pin "1") (pinfunction "1_1") (pintype "passive"))
      (node (ref "U3") (pin "6") (pinfunction "-IN_6") (pintype "input"))
    )
    (net (code "51") (name "Net-(U3B-OUT)") (class "Default")
      (node (ref "R16") (pin "2") (pinfunction "2_2") (pintype "passive"))
      (node (ref "R17") (pin "1") (pinfunction "1_1") (pintype "passive"))
      (node (ref "R18") (pin "1") (pinfunction "1_1") (pintype "passive"))
      (node (ref "U3") (pin "7") (pinfunction "OUT_7") (pintype "output"))
    )
    (net (code "52") (name "Net-(U3C-+IN)") (class "Default")
      (node (ref "R17") (pin "2") (pinfunction "2_2") (pintype "passive"))
      (node (ref "R19") (pin "2") (pinfunction "2_2") (pintype "passive"))
      (node (ref "U3") (pin "10") (pinfunction "+IN_10") (pintype "input"))
    )
    (net (code "53") (name "Net-(U3C--IN)") (class "Default")
      (node (ref "C4") (pin "1") (pinfunction "1_1") (pintype "passive"))
      (node (ref "R18") (pin "2") (pinfunction "2_2") (pintype "passive"))
      (node (ref "R22") (pin "2") (pinfunction "2_2") (pintype "passive"))
      (node (ref "U3") (pin "9") (pinfunction "-IN_9") (pintype "input"))
    )
    (net (code "54") (name "Net-(U3C-OUT)") (class "Default")
      (node (ref "C4") (pin "2") (pinfunction "2_2") (pintype "passive"))
      (node (ref "C7") (pin "+") (pinfunction "+_+") (pintype "passive"))
      (node (ref "R21") (pin "1") (pinfunction "1_1") (pintype "passive"))
      (node (ref "U3") (pin "8") (pinfunction "OUT_8") (pintype "output"))
    )
    (net (code "55") (name "Net-(U3D-+IN)") (class "Default")
      (node (ref "R24") (pin "1") (pinfunction "1_1") (pintype "passive"))
      (node (ref "R27") (pin "1") (pinfunction "1_1") (pintype "passive"))
      (node (ref "U3") (pin "12") (pinfunction "+IN_12") (pintype "input"))
    )
    (net (code "56") (name "Net-(U3D--IN)") (class "Default")
      (node (ref "R21") (pin "2") (pinfunction "2_2") (pintype "passive"))
      (node (ref "U3") (pin "13") (pinfunction "-IN_13") (pintype "input"))
    )
    (net (code "57") (name "Net-(U4-+IN)") (class "Default")
      (node (ref "C12") (pin "2") (pinfunction "2_2") (pintype "passive"))
      (node (ref "R36") (pin "2") (pinfunction "2_2") (pintype "passive"))
      (node (ref "U4") (pin "3") (pinfunction "+IN_3") (pintype "input"))
    )
    (net (code "58") (name "Net-(U4-OUT)") (class "Default")
      (node (ref "C5") (pin "1") (pinfunction "1_1") (pintype "passive"))
      (node (ref "C9") (pin "2") (pinfunction "2_2") (pintype "passive"))
      (node (ref "R35") (pin "1") (pinfunction "1_1") (pintype "passive"))
      (node (ref "U4") (pin "6") (pinfunction "OUT_6") (pintype "output"))
    )
    (net (code "59") (name "Net-(VCO-A)") (class "Default")
      (node (ref "R11") (pin "2") (pinfunction "2_2") (pintype "passive"))
      (node (ref "VCO") (pin "P$3") (pinfunction "A_P$3") (pintype "passive"))
    )
    (net (code "60") (name "Net-(VCO-E)") (class "Default")
      (node (ref "R10") (pin "2") (pinfunction "2_2") (pintype "passive"))
      (node (ref "VCO") (pin "P$1") (pinfunction "E_P$1") (pintype "passive"))
    )
    (net (code "61") (name "Net-(X1-Pad1)") (class "Default")
      (node (ref "X1") (pin "1") (pinfunction "1_1") (pintype "passive"))
      (node (ref "X2") (pin "1") (pinfunction "1_1") (pintype "passive"))
    )
    (net (code "62") (name "Net-(X1-Pad2)") (class "Default")
      (node (ref "X1") (pin "2") (pinfunction "2_2") (pintype "passive"))
      (node (ref "X2") (pin "2") (pinfunction "2_2") (pintype "passive"))
    )
    (net (code "63") (name "Net-(X1-Pad3)") (class "Default")
      (node (ref "X1") (pin "3") (pinfunction "3_3") (pintype "passive"))
      (node (ref "X2") (pin "3") (pinfunction "3_3") (pintype "passive"))
    )
    (net (code "64") (name "OUT") (class "Default")
      (node (ref "LEVEL") (pin "P$1") (pinfunction "E_P$1") (pintype "passive"))
      (node (ref "R32") (pin "2") (pinfunction "2_2") (pintype "passive"))
    )
    (net (code "65") (name "S0") (class "Default")
      (node (ref "R23") (pin "1") (pinfunction "1_1") (pintype "passive"))
      (node (ref "R24") (pin "2") (pinfunction "2_2") (pintype "passive"))
      (node (ref "U3") (pin "14") (pinfunction "OUT_14") (pintype "output"))
    )
    (net (code "66") (name "S1") (class "Default")
      (node (ref "R7") (pin "1") (pinfunction "1_1") (pintype "passive"))
      (node (ref "R8") (pin "2") (pinfunction "2_2") (pintype "passive"))
      (node (ref "U2") (pin "8") (pinfunction "OUT_8") (pintype "output"))
    )
    (net (code "67") (name "S2") (class "Default")
      (node (ref "C3") (pin "2") (pinfunction "2_2") (pintype "passive"))
      (node (ref "LFO_RATE") (pin "P$1") (pinfunction "E_P$1") (pintype "passive"))
      (node (ref "U2") (pin "12") (pinfunction "+IN_12") (pintype "input"))
      (node (ref "U2") (pin "9") (pinfunction "-IN_9") (pintype "input"))
    )
    (net (code "68") (name "S3") (class "Default")
      (node (ref "LFO_RATE") (pin "P$2") (pinfunction "S_P$2") (pintype "passive"))
      (node (ref "LFO_RATE") (pin "P$3") (pinfunction "A_P$3") (pintype "passive"))
      (node (ref "R8") (pin "1") (pinfunction "1_1") (pintype "passive"))
    )
    (net (code "69") (name "SWEEP2") (class "Default")
      (node (ref "R4") (pin "1") (pinfunction "1_1") (pintype "passive"))
      (node (ref "SWEEP") (pin "P$2") (pinfunction "S_P$2") (pintype "passive"))
    )
    (net (code "70") (name "SWEEP3") (class "Default")
      (node (ref "C2") (pin "+") (pinfunction "+_+") (pintype "passive"))
      (node (ref "D2") (pin "C") (pinfunction "C_C") (pintype "passive"))
      (node (ref "SWEEP") (pin "P$1") (pinfunction "E_P$1") (pintype "passive"))
    )
    (net (code "71") (name "TRIGGER") (class "Default")
      (node (ref "RV1") (pin "B") (pinfunction "WIPER_B") (pintype "passive"))
      (node (ref "U2") (pin "5") (pinfunction "+IN_5") (pintype "input"))
    )
    (net (code "72") (name "VCC") (class "Default")
      (node (ref "C101") (pin "+") (pinfunction "+_+") (pintype "passive"))
      (node (ref "C22") (pin "2") (pinfunction "2_2") (pintype "passive"))
      (node (ref "IC2") (pin "5") (pinfunction "IN_5") (pintype "input"))
      (node (ref "IC2") (pin "6") (pinfunction "IN_6") (pintype "input"))
      (node (ref "IC3") (pin "3") (pinfunction "VDD_3") (pintype "power_in"))
      (node (ref "R10") (pin "1") (pinfunction "1_1") (pintype "passive"))
      (node (ref "R25") (pin "2") (pinfunction "2_2") (pintype "passive"))
      (node (ref "R37") (pin "1") (pinfunction "1_1") (pintype "passive"))
      (node (ref "R39") (pin "2") (pinfunction "2_2") (pintype "passive"))
      (node (ref "R42") (pin "2") (pinfunction "2_2") (pintype "passive"))
      (node (ref "R5") (pin "2") (pinfunction "2_2") (pintype "passive"))
      (node (ref "TP3") (pin "P$1") (pinfunction "1_P$1") (pintype "bidirectional"))
      (node (ref "U$4") (pin "8") (pinfunction "VCC_8") (pintype "bidirectional"))
      (node (ref "U1") (pin "11") (pinfunction "V+_11") (pintype "bidirectional"))
      (node (ref "U100") (pin "VOUT") (pinfunction "OUT_VOUT") (pintype "bidirectional"))
      (node (ref "U2") (pin "4") (pinfunction "V+_4") (pintype "power_in"))
      (node (ref "U3") (pin "4") (pinfunction "V+_4") (pintype "power_in"))
      (node (ref "U4") (pin "7") (pinfunction "V+_7") (pintype "power_in"))
    )
    (net (code "73") (name "VCO2") (class "Default")
      (node (ref "R12") (pin "1") (pinfunction "1_1") (pintype "passive"))
      (node (ref "VCO") (pin "P$2") (pinfunction "S_P$2") (pintype "passive"))
    )
    (net (code "74") (name "VDD") (class "Default")
      (node (ref "C14") (pin "2") (pinfunction "2_2") (pintype "passive"))
      (node (ref "C15") (pin "2") (pinfunction "2_2") (pintype "passive"))
      (node (ref "C17") (pin "1") (pinfunction "1_1") (pintype "passive"))
      (node (ref "C19") (pin "2") (pinfunction "2_2") (pintype "passive"))
      (node (ref "C20") (pin "2") (pinfunction "2_2") (pintype "passive"))
      (node (ref "C21") (pin "2") (pinfunction "2_2") (pintype "passive"))
      (node (ref "C23") (pin "2") (pinfunction "2_2") (pintype "passive"))
      (node (ref "IC1") (pin "11") (pinfunction "VDD_11") (pintype "power_in"))
      (node (ref "IC1") (pin "2") (pinfunction "VDDA_2") (pintype "power_in"))
      (node (ref "IC1") (pin "26") (pinfunction "VDD_26") (pintype "power_in"))
      (node (ref "IC1") (pin "42") (pinfunction "VDD_42") (pintype "power_in"))
      (node (ref "IC1") (pin "54") (pinfunction "VDD_54") (pintype "power_in"))
      (node (ref "IC2") (pin "1") (pinfunction "FB\\SENSE_1") (pintype "input"))
      (node (ref "IC2") (pin "7") (pinfunction "OUT_7") (pintype "output"))
      (node (ref "IC2") (pin "8") (pinfunction "OUT_8") (pintype "passive"))
      (node (ref "R40") (pin "2") (pinfunction "2_2") (pintype "passive"))
      (node (ref "TP4") (pin "P$1") (pinfunction "1_P$1") (pintype "bidirectional"))
    )
    (net (code "75") (name "unconnected-(IC1-OSC0-Pad40)") (class "Default")
      (node (ref "IC1") (pin "40") (pinfunction "OSC0_40") (pintype "passive"))
    )
    (net (code "76") (name "unconnected-(IC1-OSC1-Pad41)") (class "Default")
      (node (ref "IC1") (pin "41") (pinfunction "OSC1_41") (pintype "passive"))
    )
    (net (code "77") (name "unconnected-(IC1-PA1_U0TX-Pad18)") (class "Default")
      (node (ref "IC1") (pin "18") (pinfunction "PA1_U0TX_18") (pintype "bidirectional"))
    )
    (net (code "78") (name "unconnected-(IC1-PA4_SSI0RX-Pad21)") (class "Default")
      (node (ref "IC1") (pin "21") (pinfunction "PA4_SSI0RX_21") (pintype "bidirectional"))
    )
    (net (code "79") (name "unconnected-(IC1-PA6-Pad23)") (class "Default")
      (node (ref "IC1") (pin "23") (pinfunction "PA6_23") (pintype "bidirectional"))
    )
    (net (code "80") (name "unconnected-(IC1-PA7-Pad24)") (class "Default")
      (node (ref "IC1") (pin "24") (pinfunction "PA7_24") (pintype "bidirectional"))
    )
    (net (code "81") (name "unconnected-(IC1-PB0-Pad45)") (class "Default")
      (node (ref "IC1") (pin "45") (pinfunction "PB0_45") (pintype "bidirectional"))
    )
    (net (code "82") (name "unconnected-(IC1-PB1-Pad46)") (class "Default")
      (node (ref "IC1") (pin "46") (pinfunction "PB1_46") (pintype "bidirectional"))
    )
    (net (code "83") (name "unconnected-(IC1-PB2_I2C0SCL-Pad47)") (class "Default")
      (node (ref "IC1") (pin "47") (pinfunction "PB2_I2C0SCL_47") (pintype "bidirectional"))
    )
    (net (code "84") (name "unconnected-(IC1-PB3_I2C0SDA-Pad48)") (class "Default")
      (node (ref "IC1") (pin "48") (pinfunction "PB3_I2C0SDA_48") (pintype "bidirectional"))
    )
    (net (code "85") (name "unconnected-(IC1-PB4-Pad58)") (class "Default")
      (node (ref "IC1") (pin "58") (pinfunction "PB4_58") (pintype "bidirectional"))
    )
    (net (code "86") (name "unconnected-(IC1-PB5-Pad57)") (class "Default")
      (node (ref "IC1") (pin "57") (pinfunction "PB5_57") (pintype "bidirectional"))
    )
    (net (code "87") (name "unconnected-(IC1-PB6-Pad1)") (class "Default")
      (node (ref "IC1") (pin "1") (pinfunction "PB6_1") (pintype "bidirectional"))
    )
    (net (code "88") (name "unconnected-(IC1-PB7-Pad4)") (class "Default")
      (node (ref "IC1") (pin "4") (pinfunction "PB7_4") (pintype "bidirectional"))
    )
    (net (code "89") (name "unconnected-(IC1-PC4-Pad16)") (class "Default")
      (node (ref "IC1") (pin "16") (pinfunction "PC4_16") (pintype "bidirectional"))
    )
    (net (code "90") (name "unconnected-(IC1-PC5-Pad15)") (class "Default")
      (node (ref "IC1") (pin "15") (pinfunction "PC5_15") (pintype "bidirectional"))
    )
    (net (code "91") (name "unconnected-(IC1-PC6-Pad14)") (class "Default")
      (node (ref "IC1") (pin "14") (pinfunction "PC6_14") (pintype "bidirectional"))
    )
    (net (code "92") (name "unconnected-(IC1-PC7-Pad13)") (class "Default")
      (node (ref "IC1") (pin "13") (pinfunction "PC7_13") (pintype "bidirectional"))
    )
    (net (code "93") (name "unconnected-(IC1-PD1-Pad62)") (class "Default")
      (node (ref "IC1") (pin "62") (pinfunction "PD1_62") (pintype "bidirectional"))
    )
    (net (code "94") (name "unconnected-(IC1-PD2-Pad63)") (class "Default")
      (node (ref "IC1") (pin "63") (pinfunction "PD2_63") (pintype "bidirectional"))
    )
    (net (code "95") (name "unconnected-(IC1-PD3-Pad64)") (class "Default")
      (node (ref "IC1") (pin "64") (pinfunction "PD3_64") (pintype "bidirectional"))
    )
    (net (code "96") (name "unconnected-(IC1-PD4-Pad43)") (class "Default")
      (node (ref "IC1") (pin "43") (pinfunction "PD4_43") (pintype "bidirectional"))
    )
    (net (code "97") (name "unconnected-(IC1-PD5-Pad44)") (class "Default")
      (node (ref "IC1") (pin "44") (pinfunction "PD5_44") (pintype "bidirectional"))
    )
    (net (code "98") (name "unconnected-(IC1-PD6-Pad53)") (class "Default")
      (node (ref "IC1") (pin "53") (pinfunction "PD6_53") (pintype "bidirectional"))
    )
    (net (code "99") (name "unconnected-(IC1-PD7-Pad10)") (class "Default")
      (node (ref "IC1") (pin "10") (pinfunction "PD7_10") (pintype "bidirectional"))
    )
    (net (code "100") (name "unconnected-(IC1-PE0-Pad9)") (class "Default")
      (node (ref "IC1") (pin "9") (pinfunction "PE0_9") (pintype "bidirectional"))
    )
    (net (code "101") (name "unconnected-(IC1-PE1-Pad8)") (class "Default")
      (node (ref "IC1") (pin "8") (pinfunction "PE1_8") (pintype "bidirectional"))
    )
    (net (code "102") (name "unconnected-(IC1-PE2-Pad7)") (class "Default")
      (node (ref "IC1") (pin "7") (pinfunction "PE2_7") (pintype "bidirectional"))
    )
    (net (code "103") (name "unconnected-(IC1-PE3-Pad6)") (class "Default")
      (node (ref "IC1") (pin "6") (pinfunction "PE3_6") (pintype "bidirectional"))
    )
    (net (code "104") (name "unconnected-(IC1-PE4-Pad59)") (class "Default")
      (node (ref "IC1") (pin "59") (pinfunction "PE4_59") (pintype "bidirectional"))
    )
    (net (code "105") (name "unconnected-(IC1-PE5-Pad60)") (class "Default")
      (node (ref "IC1") (pin "60") (pinfunction "PE5_60") (pintype "bidirectional"))
    )
    (net (code "106") (name "unconnected-(IC1-PF0-Pad28)") (class "Default")
      (node (ref "IC1") (pin "28") (pinfunction "PF0_28") (pintype "bidirectional"))
    )
    (net (code "107") (name "unconnected-(IC1-PF1-Pad29)") (class "Default")
      (node (ref "IC1") (pin "29") (pinfunction "PF1_29") (pintype "bidirectional"))
    )
    (net (code "108") (name "unconnected-(IC1-PF2-Pad30)") (class "Default")
      (node (ref "IC1") (pin "30") (pinfunction "PF2_30") (pintype "bidirectional"))
    )
    (net (code "109") (name "unconnected-(IC1-PF3-Pad31)") (class "Default")
      (node (ref "IC1") (pin "31") (pinfunction "PF3_31") (pintype "bidirectional"))
    )
    (net (code "110") (name "unconnected-(IC1-PF4-Pad5)") (class "Default")
      (node (ref "IC1") (pin "5") (pinfunction "PF4_5") (pintype "bidirectional"))
    )
    (net (code "111") (name "unconnected-(IC1-PG0-Pad37)") (class "Default")
      (node (ref "IC1") (pin "37") (pinfunction "PG0_37") (pintype "bidirectional"))
    )
    (net (code "112") (name "unconnected-(IC1-PG1-Pad36)") (class "Default")
      (node (ref "IC1") (pin "36") (pinfunction "PG1_36") (pintype "bidirectional"))
    )
    (net (code "113") (name "unconnected-(IC1-PG2-Pad35)") (class "Default")
      (node (ref "IC1") (pin "35") (pinfunction "PG2_35") (pintype "bidirectional"))
    )
    (net (code "114") (name "unconnected-(IC1-PG3-Pad34)") (class "Default")
      (node (ref "IC1") (pin "34") (pinfunction "PG3_34") (pintype "bidirectional"))
    )
    (net (code "115") (name "unconnected-(IC1-PG4-Pad33)") (class "Default")
      (node (ref "IC1") (pin "33") (pinfunction "PG4_33") (pintype "bidirectional"))
    )
    (net (code "116") (name "unconnected-(IC1-PG5-Pad32)") (class "Default")
      (node (ref "IC1") (pin "32") (pinfunction "PG5_32") (pintype "bidirectional"))
    )
    (net (code "117") (name "unconnected-(IC2-~{RESET}-Pad2)") (class "Default")
      (node (ref "IC2") (pin "2") (pinfunction "~{RESET}_2") (pintype "input"))
    )
    (net (code "118") (name "unconnected-(Q2-C-Pad3)") (class "Default")
      (node (ref "Q2") (pin "3") (pinfunction "C_3") (pintype "passive"))
    )
    (net (code "119") (name "unconnected-(U$1-PadRN)") (class "Default")
      (node (ref "U$1") (pin "RN") (pinfunction "RN_RN") (pintype "bidirectional"))
    )
    (net (code "120") (name "unconnected-(U$1-PadSN)") (class "Default")
      (node (ref "U$1") (pin "SN") (pinfunction "SN_SN") (pintype "bidirectional"))
    )
    (net (code "121") (name "unconnected-(U$1-PadTN)") (class "Default")
      (node (ref "U$1") (pin "TN") (pinfunction "TN_TN") (pintype "bidirectional"))
    )
    (net (code "122") (name "unconnected-(U$3-PadP$10)") (class "Default")
      (node (ref "U$3") (pin "P$10") (pinfunction "P$10_P$10") (pintype "bidirectional"))
    )
    (net (code "123") (name "unconnected-(U1A-ID-Pad2)") (class "Default")
      (node (ref "U1") (pin "2") (pinfunction "ID_2") (pintype "bidirectional"))
    )
    (net (code "124") (name "unconnected-(U1B-+IN-Pad14)") (class "Default")
      (node (ref "U1") (pin "14") (pinfunction "+IN_14") (pintype "bidirectional"))
    )
    (net (code "125") (name "unconnected-(U1B--IN-Pad13)") (class "Default")
      (node (ref "U1") (pin "13") (pinfunction "-IN_13") (pintype "bidirectional"))
    )
    (net (code "126") (name "unconnected-(U1B-IABC-Pad16)") (class "Default")
      (node (ref "U1") (pin "16") (pinfunction "IABC_16") (pintype "bidirectional"))
    )
    (net (code "127") (name "unconnected-(U1B-ID-Pad15)") (class "Default")
      (node (ref "U1") (pin "15") (pinfunction "ID_15") (pintype "bidirectional"))
    )
    (net (code "128") (name "unconnected-(U1B-OUT-Pad12)") (class "Default")
      (node (ref "U1") (pin "12") (pinfunction "OUT_12") (pintype "bidirectional"))
    )
    (net (code "129") (name "unconnected-(U1C-IN-Pad7)") (class "Default")
      (node (ref "U1") (pin "7") (pinfunction "IN_7") (pintype "bidirectional"))
    )
    (net (code "130") (name "unconnected-(U1C-OUT-Pad8)") (class "Default")
      (node (ref "U1") (pin "8") (pinfunction "OUT_8") (pintype "bidirectional"))
    )
    (net (code "131") (name "unconnected-(U1D-IN-Pad10)") (class "Default")
      (node (ref "U1") (pin "10") (pinfunction "IN_10") (pintype "bidirectional"))
    )
    (net (code "132") (name "unconnected-(U1D-OUT-Pad9)") (class "Default")
      (node (ref "U1") (pin "9") (pinfunction "OUT_9") (pintype "bidirectional"))
    )
    (net (code "133") (name "unconnected-(U4-ON1-Pad1)") (class "Default")
      (node (ref "U4") (pin "1") (pinfunction "ON1_1") (pintype "passive"))
    )
    (net (code "134") (name "unconnected-(U4-ON2-Pad5)") (class "Default")
      (node (ref "U4") (pin "5") (pinfunction "ON2_5") (pintype "passive"))
    )
    (net (code "135") (name "unconnected-(U4-OPT-Pad8)") (class "Default")
      (node (ref "U4") (pin "8") (pinfunction "OPT_8") (pintype "passive"))
    )
  )
)
